# mcu0_primary.net
KiCad netlist of a schematic drawn in Altium Designer
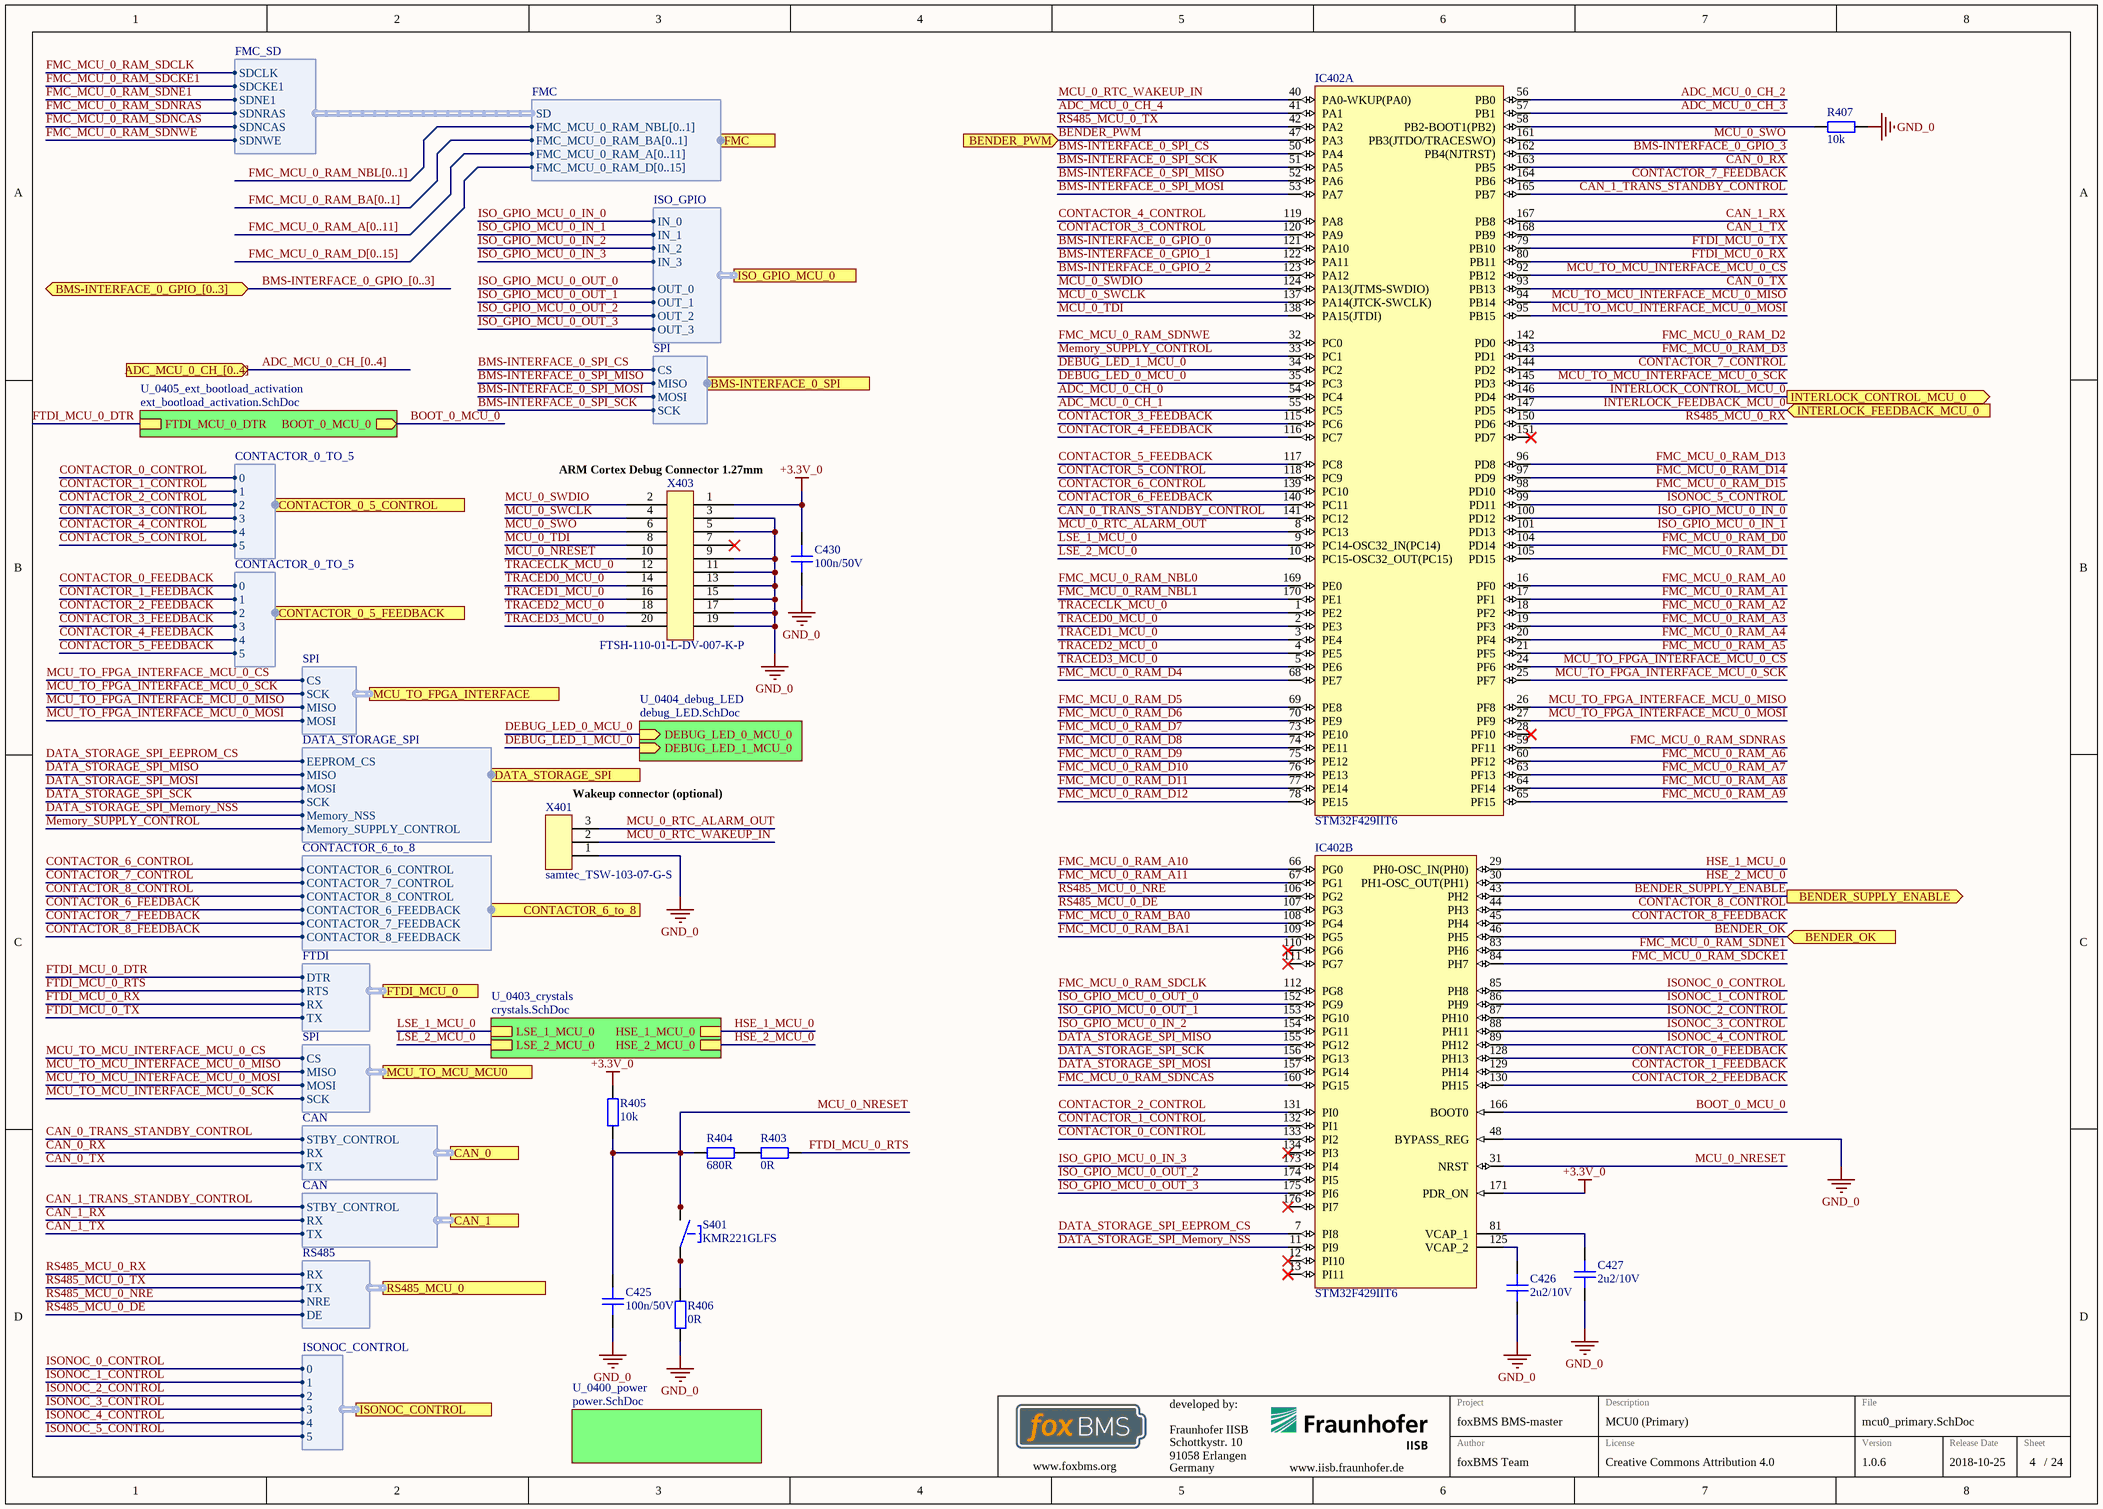
[diagram p0: mcu0_primary.SchDoc]

(export (version "E")
  (design (tool "Eeschema 10.0.6"))
  (components
    (comp (ref "C425")
      (value "100n/50V")
      (footprint "CAPC1608X08N")
      (description "MLCC")
      (fields (field (name "PART NUMBER") "gen_C_ceramic_100n_50V_X7R_0603"))
      (libsource (lib "OE750") (part "C"))
    )
    (comp (ref "C426")
      (value "2u2/10V")
      (footprint "CAPC1608X08N")
      (description "MLCC")
      (fields (field (name "PART NUMBER") "gen_C_ceramic_2u2_10V_X5R_0603"))
      (libsource (lib "OE750") (part "C"))
    )
    (comp (ref "C427")
      (value "2u2/10V")
      (footprint "CAPC1608X08N")
      (description "MLCC")
      (fields (field (name "PART NUMBER") "gen_C_ceramic_2u2_10V_X5R_0603"))
      (libsource (lib "OE750") (part "C"))
    )
    (comp (ref "C430")
      (value "100n/50V")
      (footprint "CAPC1608X08N")
      (description "MLCC")
      (fields (field (name "PART NUMBER") "gen_C_ceramic_100n_50V_X7R_0603"))
      (libsource (lib "OE750") (part "C"))
    )
    (comp (ref "IC402")
      (value "STM32F429IIT6")
      (footprint "STM-LQFP176_N")
      (fields (field (name "MANUFACTURER") "STMicroelectronics"))
      (libsource (lib "Altium Content Vault") (part "MC-ARM-STM32F4X9-SQ176"))
    )
    (comp (ref "R403")
      (value "0R")
      (footprint "RESC1608X05N")
      (description "SMD Resistor 0R 0603")
      (fields (field (name "PART NUMBER") "gen_R_0R_0603") (field (name "POWER") "0.1W"))
      (libsource (lib "OE750") (part "R"))
    )
    (comp (ref "R404")
      (value "680R")
      (footprint "RESC1608X05N")
      (description "SMD Resistor 680R 0603")
      (fields (field (name "PART NUMBER") "gen_R_680R_0603") (field (name "TOLERANCE") "1%"))
      (libsource (lib "OE750") (part "R"))
    )
    (comp (ref "R405")
      (value "10k")
      (footprint "RESC1608X05N")
      (description "SMD Resistor 10k 0603")
      (fields (field (name "PART NUMBER") "gen_R_10k_0603") (field (name "TOLERANCE") "1%"))
      (libsource (lib "OE750") (part "R"))
    )
    (comp (ref "R406")
      (value "0R")
      (footprint "RESC1608X05N")
      (description "SMD Resistor 0R 0603")
      (fields (field (name "PART NUMBER") "gen_R_0R_0603") (field (name "POWER") "0.1W"))
      (libsource (lib "OE750") (part "R"))
    )
    (comp (ref "R407")
      (value "10k")
      (footprint "RESC1608X05N")
      (description "SMD Resistor 10k 0603")
      (fields (field (name "PART NUMBER") "gen_R_10k_0603") (field (name "TOLERANCE") "1%"))
      (libsource (lib "OE750") (part "R"))
    )
    (comp (ref "S401")
      (value "KMR221GLFS")
      (footprint "KMR2_Series")
      (description "Microminiature Tactile Switch")
      (fields (field (name "MANUFACTURER") "CK Components"))
      (libsource (lib "OE750") (part "Switch_4_Pin"))
    )
    (comp (ref "X401")
      (value "samtec_TSW-103-07-G-S")
      (footprint "Pinheader_2.54_3")
      (description "Board-To-Board Connector, Vertical, 2.54 mm, 3 Contacts, Header, TSW Series, Through Hole, 1 Row")
      (fields (field (name "MANUFACTURER") "Samtec"))
      (libsource (lib "OE750") (part "X3"))
    )
    (comp (ref "X403")
      (value "FTSH-110-01-L-DV-007-K-P")
      (footprint "CORTEX_DEBUG_20_PIN")
      (description "Board-To-Board Connector, ARM Cortex Debug Header 20 Pin")
      (fields
        (field (name "PART NUMBER") "samtec_FTSH-110-01-L-DV-007-K-P")
        (field (name "MANUFACTURER") "Samtec")
      )
      (libsource (lib "OE750") (part "CORTEX_DEBUG_20_PIN"))
    )
  )
  (nets
    (net (code "12") (name "+3.3V_0") (class "Default")
      (node (ref "C430") (pin "1") (pinfunction "1_1") (pintype "passive"))
      (node (ref "IC402") (pin "171") (pinfunction "PDR_ON_171") (pintype "input"))
      (node (ref "R405") (pin "2") (pinfunction "2_2") (pintype "passive"))
      (node (ref "X403") (pin "1") (pintype "passive"))
    )
    (net (code "13") (name "/ADC_MCU_0_CH_0") (class "Default")
      (node (ref "IC402") (pin "54") (pinfunction "PC4_54") (pintype "bidirectional"))
    )
    (net (code "14") (name "/ADC_MCU_0_CH_1") (class "Default")
      (node (ref "IC402") (pin "55") (pinfunction "PC5_55") (pintype "bidirectional"))
    )
    (net (code "15") (name "/ADC_MCU_0_CH_2") (class "Default")
      (node (ref "IC402") (pin "56") (pinfunction "PB0_56") (pintype "bidirectional"))
    )
    (net (code "16") (name "/ADC_MCU_0_CH_3") (class "Default")
      (node (ref "IC402") (pin "57") (pinfunction "PB1_57") (pintype "bidirectional"))
    )
    (net (code "17") (name "/ADC_MCU_0_CH_4") (class "Default")
      (node (ref "IC402") (pin "41") (pinfunction "PA1_41") (pintype "bidirectional"))
    )
    (net (code "19") (name "/BENDER_OK") (class "Default")
      (node (ref "IC402") (pin "46") (pinfunction "PH5_46") (pintype "bidirectional"))
    )
    (net (code "20") (name "/BENDER_PWM") (class "Default")
      (node (ref "IC402") (pin "47") (pinfunction "PA3_47") (pintype "bidirectional"))
    )
    (net (code "21") (name "/BENDER_SUPPLY_ENABLE") (class "Default")
      (node (ref "IC402") (pin "43") (pinfunction "PH2_43") (pintype "bidirectional"))
    )
    (net (code "22") (name "/BMS-INTERFACE_0_GPIO_0") (class "Default")
      (node (ref "IC402") (pin "121") (pinfunction "PA10_121") (pintype "bidirectional"))
    )
    (net (code "23") (name "/BMS-INTERFACE_0_GPIO_1") (class "Default")
      (node (ref "IC402") (pin "122") (pinfunction "PA11_122") (pintype "bidirectional"))
    )
    (net (code "24") (name "/BMS-INTERFACE_0_GPIO_2") (class "Default")
      (node (ref "IC402") (pin "123") (pinfunction "PA12_123") (pintype "bidirectional"))
    )
    (net (code "25") (name "/BMS-INTERFACE_0_GPIO_3") (class "Default")
      (node (ref "IC402") (pin "162") (pinfunction "PB4(NJTRST)_162") (pintype "bidirectional"))
    )
    (net (code "27") (name "/BMS-INTERFACE_0_SPI_CS") (class "Default")
      (node (ref "IC402") (pin "50") (pinfunction "PA4_50") (pintype "bidirectional"))
    )
    (net (code "28") (name "/BMS-INTERFACE_0_SPI_MISO") (class "Default")
      (node (ref "IC402") (pin "52") (pinfunction "PA6_52") (pintype "bidirectional"))
    )
    (net (code "29") (name "/BMS-INTERFACE_0_SPI_MOSI") (class "Default")
      (node (ref "IC402") (pin "53") (pinfunction "PA7_53") (pintype "bidirectional"))
    )
    (net (code "30") (name "/BMS-INTERFACE_0_SPI_SCK") (class "Default")
      (node (ref "IC402") (pin "51") (pinfunction "PA5_51") (pintype "bidirectional"))
    )
    (net (code "31") (name "/BOOT_0_MCU_0") (class "Default")
      (node (ref "IC402") (pin "166") (pinfunction "BOOT0_166") (pintype "input"))
    )
    (net (code "32") (name "/CAN_0_RX") (class "Default")
      (node (ref "IC402") (pin "163") (pinfunction "PB5_163") (pintype "bidirectional"))
    )
    (net (code "33") (name "/CAN_0_TRANS_STANDBY_CONTROL") (class "Default")
      (node (ref "IC402") (pin "141") (pinfunction "PC12_141") (pintype "bidirectional"))
    )
    (net (code "34") (name "/CAN_0_TX") (class "Default")
      (node (ref "IC402") (pin "93") (pinfunction "PB13_93") (pintype "bidirectional"))
    )
    (net (code "35") (name "/CAN_1_RX") (class "Default")
      (node (ref "IC402") (pin "167") (pinfunction "PB8_167") (pintype "bidirectional"))
    )
    (net (code "36") (name "/CAN_1_TRANS_STANDBY_CONTROL") (class "Default")
      (node (ref "IC402") (pin "165") (pinfunction "PB7_165") (pintype "bidirectional"))
    )
    (net (code "37") (name "/CAN_1_TX") (class "Default")
      (node (ref "IC402") (pin "168") (pinfunction "PB9_168") (pintype "bidirectional"))
    )
    (net (code "38") (name "/CONTACTOR_0_CONTROL") (class "Default")
      (node (ref "IC402") (pin "133") (pinfunction "PI2_133") (pintype "bidirectional"))
    )
    (net (code "39") (name "/CONTACTOR_0_FEEDBACK") (class "Default")
      (node (ref "IC402") (pin "128") (pinfunction "PH13_128") (pintype "bidirectional"))
    )
    (net (code "40") (name "/CONTACTOR_1_CONTROL") (class "Default")
      (node (ref "IC402") (pin "132") (pinfunction "PI1_132") (pintype "bidirectional"))
    )
    (net (code "41") (name "/CONTACTOR_1_FEEDBACK") (class "Default")
      (node (ref "IC402") (pin "129") (pinfunction "PH14_129") (pintype "bidirectional"))
    )
    (net (code "42") (name "/CONTACTOR_2_CONTROL") (class "Default")
      (node (ref "IC402") (pin "131") (pinfunction "PI0_131") (pintype "bidirectional"))
    )
    (net (code "43") (name "/CONTACTOR_2_FEEDBACK") (class "Default")
      (node (ref "IC402") (pin "130") (pinfunction "PH15_130") (pintype "bidirectional"))
    )
    (net (code "44") (name "/CONTACTOR_3_CONTROL") (class "Default")
      (node (ref "IC402") (pin "120") (pinfunction "PA9_120") (pintype "bidirectional"))
    )
    (net (code "45") (name "/CONTACTOR_3_FEEDBACK") (class "Default")
      (node (ref "IC402") (pin "115") (pinfunction "PC6_115") (pintype "bidirectional"))
    )
    (net (code "46") (name "/CONTACTOR_4_CONTROL") (class "Default")
      (node (ref "IC402") (pin "119") (pinfunction "PA8_119") (pintype "bidirectional"))
    )
    (net (code "47") (name "/CONTACTOR_4_FEEDBACK") (class "Default")
      (node (ref "IC402") (pin "116") (pinfunction "PC7_116") (pintype "bidirectional"))
    )
    (net (code "48") (name "/CONTACTOR_5_CONTROL") (class "Default")
      (node (ref "IC402") (pin "118") (pinfunction "PC9_118") (pintype "bidirectional"))
    )
    (net (code "49") (name "/CONTACTOR_5_FEEDBACK") (class "Default")
      (node (ref "IC402") (pin "117") (pinfunction "PC8_117") (pintype "bidirectional"))
    )
    (net (code "50") (name "/CONTACTOR_6_CONTROL") (class "Default")
      (node (ref "IC402") (pin "139") (pinfunction "PC10_139") (pintype "bidirectional"))
    )
    (net (code "51") (name "/CONTACTOR_6_FEEDBACK") (class "Default")
      (node (ref "IC402") (pin "140") (pinfunction "PC11_140") (pintype "bidirectional"))
    )
    (net (code "52") (name "/CONTACTOR_7_CONTROL") (class "Default")
      (node (ref "IC402") (pin "144") (pinfunction "PD2_144") (pintype "bidirectional"))
    )
    (net (code "53") (name "/CONTACTOR_7_FEEDBACK") (class "Default")
      (node (ref "IC402") (pin "164") (pinfunction "PB6_164") (pintype "bidirectional"))
    )
    (net (code "54") (name "/CONTACTOR_8_CONTROL") (class "Default")
      (node (ref "IC402") (pin "44") (pinfunction "PH3_44") (pintype "bidirectional"))
    )
    (net (code "55") (name "/CONTACTOR_8_FEEDBACK") (class "Default")
      (node (ref "IC402") (pin "45") (pinfunction "PH4_45") (pintype "bidirectional"))
    )
    (net (code "56") (name "/DATA_STORAGE_SPI_EEPROM_CS") (class "Default")
      (node (ref "IC402") (pin "7") (pinfunction "PI8_7") (pintype "bidirectional"))
    )
    (net (code "57") (name "/DATA_STORAGE_SPI_MISO") (class "Default")
      (node (ref "IC402") (pin "155") (pinfunction "PG12_155") (pintype "bidirectional"))
    )
    (net (code "58") (name "/DATA_STORAGE_SPI_MOSI") (class "Default")
      (node (ref "IC402") (pin "157") (pinfunction "PG14_157") (pintype "bidirectional"))
    )
    (net (code "59") (name "/DATA_STORAGE_SPI_Memory_NSS") (class "Default")
      (node (ref "IC402") (pin "11") (pinfunction "PI9_11") (pintype "bidirectional"))
    )
    (net (code "60") (name "/DATA_STORAGE_SPI_SCK") (class "Default")
      (node (ref "IC402") (pin "156") (pinfunction "PG13_156") (pintype "bidirectional"))
    )
    (net (code "61") (name "/DEBUG_LED_0_MCU_0") (class "Default")
      (node (ref "IC402") (pin "35") (pinfunction "PC3_35") (pintype "bidirectional"))
    )
    (net (code "62") (name "/DEBUG_LED_1_MCU_0") (class "Default")
      (node (ref "IC402") (pin "34") (pinfunction "PC2_34") (pintype "bidirectional"))
    )
    (net (code "63") (name "/FMC_MCU_0_RAM_A0") (class "Default")
      (node (ref "IC402") (pin "16") (pinfunction "PF0_16") (pintype "bidirectional"))
    )
    (net (code "64") (name "/FMC_MCU_0_RAM_A1") (class "Default")
      (node (ref "IC402") (pin "17") (pinfunction "PF1_17") (pintype "bidirectional"))
    )
    (net (code "65") (name "/FMC_MCU_0_RAM_A2") (class "Default")
      (node (ref "IC402") (pin "18") (pinfunction "PF2_18") (pintype "bidirectional"))
    )
    (net (code "66") (name "/FMC_MCU_0_RAM_A3") (class "Default")
      (node (ref "IC402") (pin "19") (pinfunction "PF3_19") (pintype "bidirectional"))
    )
    (net (code "67") (name "/FMC_MCU_0_RAM_A4") (class "Default")
      (node (ref "IC402") (pin "20") (pinfunction "PF4_20") (pintype "bidirectional"))
    )
    (net (code "68") (name "/FMC_MCU_0_RAM_A5") (class "Default")
      (node (ref "IC402") (pin "21") (pinfunction "PF5_21") (pintype "bidirectional"))
    )
    (net (code "69") (name "/FMC_MCU_0_RAM_A6") (class "Default")
      (node (ref "IC402") (pin "60") (pinfunction "PF12_60") (pintype "bidirectional"))
    )
    (net (code "70") (name "/FMC_MCU_0_RAM_A7") (class "Default")
      (node (ref "IC402") (pin "63") (pinfunction "PF13_63") (pintype "bidirectional"))
    )
    (net (code "71") (name "/FMC_MCU_0_RAM_A8") (class "Default")
      (node (ref "IC402") (pin "64") (pinfunction "PF14_64") (pintype "bidirectional"))
    )
    (net (code "72") (name "/FMC_MCU_0_RAM_A9") (class "Default")
      (node (ref "IC402") (pin "65") (pinfunction "PF15_65") (pintype "bidirectional"))
    )
    (net (code "73") (name "/FMC_MCU_0_RAM_A10") (class "Default")
      (node (ref "IC402") (pin "66") (pinfunction "PG0_66") (pintype "bidirectional"))
    )
    (net (code "74") (name "/FMC_MCU_0_RAM_A11") (class "Default")
      (node (ref "IC402") (pin "67") (pinfunction "PG1_67") (pintype "bidirectional"))
    )
    (net (code "76") (name "/FMC_MCU_0_RAM_BA0") (class "Default")
      (node (ref "IC402") (pin "108") (pinfunction "PG4_108") (pintype "bidirectional"))
    )
    (net (code "77") (name "/FMC_MCU_0_RAM_BA1") (class "Default")
      (node (ref "IC402") (pin "109") (pinfunction "PG5_109") (pintype "bidirectional"))
    )
    (net (code "79") (name "/FMC_MCU_0_RAM_D0") (class "Default")
      (node (ref "IC402") (pin "104") (pinfunction "PD14_104") (pintype "bidirectional"))
    )
    (net (code "80") (name "/FMC_MCU_0_RAM_D1") (class "Default")
      (node (ref "IC402") (pin "105") (pinfunction "PD15_105") (pintype "bidirectional"))
    )
    (net (code "81") (name "/FMC_MCU_0_RAM_D2") (class "Default")
      (node (ref "IC402") (pin "142") (pinfunction "PD0_142") (pintype "bidirectional"))
    )
    (net (code "82") (name "/FMC_MCU_0_RAM_D3") (class "Default")
      (node (ref "IC402") (pin "143") (pinfunction "PD1_143") (pintype "bidirectional"))
    )
    (net (code "83") (name "/FMC_MCU_0_RAM_D4") (class "Default")
      (node (ref "IC402") (pin "68") (pinfunction "PE7_68") (pintype "bidirectional"))
    )
    (net (code "84") (name "/FMC_MCU_0_RAM_D5") (class "Default")
      (node (ref "IC402") (pin "69") (pinfunction "PE8_69") (pintype "bidirectional"))
    )
    (net (code "85") (name "/FMC_MCU_0_RAM_D6") (class "Default")
      (node (ref "IC402") (pin "70") (pinfunction "PE9_70") (pintype "bidirectional"))
    )
    (net (code "86") (name "/FMC_MCU_0_RAM_D7") (class "Default")
      (node (ref "IC402") (pin "73") (pinfunction "PE10_73") (pintype "bidirectional"))
    )
    (net (code "87") (name "/FMC_MCU_0_RAM_D8") (class "Default")
      (node (ref "IC402") (pin "74") (pinfunction "PE11_74") (pintype "bidirectional"))
    )
    (net (code "88") (name "/FMC_MCU_0_RAM_D9") (class "Default")
      (node (ref "IC402") (pin "75") (pinfunction "PE12_75") (pintype "bidirectional"))
    )
    (net (code "89") (name "/FMC_MCU_0_RAM_D10") (class "Default")
      (node (ref "IC402") (pin "76") (pinfunction "PE13_76") (pintype "bidirectional"))
    )
    (net (code "90") (name "/FMC_MCU_0_RAM_D11") (class "Default")
      (node (ref "IC402") (pin "77") (pinfunction "PE14_77") (pintype "bidirectional"))
    )
    (net (code "91") (name "/FMC_MCU_0_RAM_D12") (class "Default")
      (node (ref "IC402") (pin "78") (pinfunction "PE15_78") (pintype "bidirectional"))
    )
    (net (code "92") (name "/FMC_MCU_0_RAM_D13") (class "Default")
      (node (ref "IC402") (pin "96") (pinfunction "PD8_96") (pintype "bidirectional"))
    )
    (net (code "93") (name "/FMC_MCU_0_RAM_D14") (class "Default")
      (node (ref "IC402") (pin "97") (pinfunction "PD9_97") (pintype "bidirectional"))
    )
    (net (code "94") (name "/FMC_MCU_0_RAM_D15") (class "Default")
      (node (ref "IC402") (pin "98") (pinfunction "PD10_98") (pintype "bidirectional"))
    )
    (net (code "95") (name "/FMC_MCU_0_RAM_NBL0") (class "Default")
      (node (ref "IC402") (pin "169") (pinfunction "PE0_169") (pintype "bidirectional"))
    )
    (net (code "96") (name "/FMC_MCU_0_RAM_NBL1") (class "Default")
      (node (ref "IC402") (pin "170") (pinfunction "PE1_170") (pintype "bidirectional"))
    )
    (net (code "98") (name "/FMC_MCU_0_RAM_SDCKE1") (class "Default")
      (node (ref "IC402") (pin "84") (pinfunction "PH7_84") (pintype "bidirectional"))
    )
    (net (code "99") (name "/FMC_MCU_0_RAM_SDCLK") (class "Default")
      (node (ref "IC402") (pin "112") (pinfunction "PG8_112") (pintype "bidirectional"))
    )
    (net (code "100") (name "/FMC_MCU_0_RAM_SDNCAS") (class "Default")
      (node (ref "IC402") (pin "160") (pinfunction "PG15_160") (pintype "bidirectional"))
    )
    (net (code "101") (name "/FMC_MCU_0_RAM_SDNE1") (class "Default")
      (node (ref "IC402") (pin "83") (pinfunction "PH6_83") (pintype "bidirectional"))
    )
    (net (code "102") (name "/FMC_MCU_0_RAM_SDNRAS") (class "Default")
      (node (ref "IC402") (pin "59") (pinfunction "PF11_59") (pintype "bidirectional"))
    )
    (net (code "103") (name "/FMC_MCU_0_RAM_SDNWE") (class "Default")
      (node (ref "IC402") (pin "32") (pinfunction "PC0_32") (pintype "bidirectional"))
    )
    (net (code "106") (name "/FTDI_MCU_0_RTS") (class "Default")
      (node (ref "R403") (pin "2") (pinfunction "2_2") (pintype "passive"))
    )
    (net (code "107") (name "/FTDI_MCU_0_RX") (class "Default")
      (node (ref "IC402") (pin "80") (pinfunction "PB11_80") (pintype "bidirectional"))
    )
    (net (code "108") (name "/FTDI_MCU_0_TX") (class "Default")
      (node (ref "IC402") (pin "79") (pinfunction "PB10_79") (pintype "bidirectional"))
    )
    (net (code "109") (name "/HSE_1_MCU_0") (class "Default")
      (node (ref "IC402") (pin "29") (pinfunction "PH0-OSC_IN(PH0)_29") (pintype "bidirectional"))
    )
    (net (code "110") (name "/HSE_2_MCU_0") (class "Default")
      (node (ref "IC402") (pin "30") (pinfunction "PH1-OSC_OUT(PH1)_30") (pintype "bidirectional"))
    )
    (net (code "111") (name "/INTERLOCK_CONTROL_MCU_0") (class "Default")
      (node (ref "IC402") (pin "146") (pinfunction "PD4_146") (pintype "bidirectional"))
    )
    (net (code "112") (name "/INTERLOCK_FEEDBACK_MCU_0") (class "Default")
      (node (ref "IC402") (pin "147") (pinfunction "PD5_147") (pintype "bidirectional"))
    )
    (net (code "113") (name "/ISONOC_0_CONTROL") (class "Default")
      (node (ref "IC402") (pin "85") (pinfunction "PH8_85") (pintype "bidirectional"))
    )
    (net (code "114") (name "/ISONOC_1_CONTROL") (class "Default")
      (node (ref "IC402") (pin "86") (pinfunction "PH9_86") (pintype "bidirectional"))
    )
    (net (code "115") (name "/ISONOC_2_CONTROL") (class "Default")
      (node (ref "IC402") (pin "87") (pinfunction "PH10_87") (pintype "bidirectional"))
    )
    (net (code "116") (name "/ISONOC_3_CONTROL") (class "Default")
      (node (ref "IC402") (pin "88") (pinfunction "PH11_88") (pintype "bidirectional"))
    )
    (net (code "117") (name "/ISONOC_4_CONTROL") (class "Default")
      (node (ref "IC402") (pin "89") (pinfunction "PH12_89") (pintype "bidirectional"))
    )
    (net (code "118") (name "/ISONOC_5_CONTROL") (class "Default")
      (node (ref "IC402") (pin "99") (pinfunction "PD11_99") (pintype "bidirectional"))
    )
    (net (code "119") (name "/ISO_GPIO_MCU_0_IN_0") (class "Default")
      (node (ref "IC402") (pin "100") (pinfunction "PD12_100") (pintype "bidirectional"))
    )
    (net (code "120") (name "/ISO_GPIO_MCU_0_IN_1") (class "Default")
      (node (ref "IC402") (pin "101") (pinfunction "PD13_101") (pintype "bidirectional"))
    )
    (net (code "121") (name "/ISO_GPIO_MCU_0_IN_2") (class "Default")
      (node (ref "IC402") (pin "154") (pinfunction "PG11_154") (pintype "bidirectional"))
    )
    (net (code "122") (name "/ISO_GPIO_MCU_0_IN_3") (class "Default")
      (node (ref "IC402") (pin "173") (pinfunction "PI4_173") (pintype "bidirectional"))
    )
    (net (code "123") (name "/ISO_GPIO_MCU_0_OUT_0") (class "Default")
      (node (ref "IC402") (pin "152") (pinfunction "PG9_152") (pintype "bidirectional"))
    )
    (net (code "124") (name "/ISO_GPIO_MCU_0_OUT_1") (class "Default")
      (node (ref "IC402") (pin "153") (pinfunction "PG10_153") (pintype "bidirectional"))
    )
    (net (code "125") (name "/ISO_GPIO_MCU_0_OUT_2") (class "Default")
      (node (ref "IC402") (pin "174") (pinfunction "PI5_174") (pintype "bidirectional"))
    )
    (net (code "126") (name "/ISO_GPIO_MCU_0_OUT_3") (class "Default")
      (node (ref "IC402") (pin "175") (pinfunction "PI6_175") (pintype "bidirectional"))
    )
    (net (code "127") (name "/LSE_1_MCU_0") (class "Default")
      (node (ref "IC402") (pin "9") (pinfunction "PC14-OSC32_IN(PC14)_9") (pintype "bidirectional"))
    )
    (net (code "128") (name "/LSE_2_MCU_0") (class "Default")
      (node (ref "IC402") (pin "10") (pinfunction "PC15-OSC32_OUT(PC15)_10") (pintype "bidirectional"))
    )
    (net (code "129") (name "/MCU_0_NRESET") (class "Default")
      (node (ref "C425") (pin "1") (pinfunction "1_1") (pintype "passive"))
      (node (ref "IC402") (pin "31") (pinfunction "NRST_31") (pintype "bidirectional"))
      (node (ref "R404") (pin "1") (pinfunction "1_1") (pintype "passive"))
      (node (ref "R405") (pin "1") (pinfunction "1_1") (pintype "passive"))
      (node (ref "S401") (pin "3") (pintype "passive"))
      (node (ref "S401") (pin "4") (pintype "passive"))
      (node (ref "X403") (pin "10") (pintype "passive"))
    )
    (net (code "130") (name "/MCU_0_RTC_ALARM_OUT") (class "Default")
      (node (ref "IC402") (pin "8") (pinfunction "PC13_8") (pintype "bidirectional"))
      (node (ref "X401") (pin "3") (pintype "passive"))
    )
    (net (code "131") (name "/MCU_0_RTC_WAKEUP_IN") (class "Default")
      (node (ref "IC402") (pin "40") (pinfunction "PA0-WKUP(PA0)_40") (pintype "bidirectional"))
      (node (ref "X401") (pin "2") (pintype "passive"))
    )
    (net (code "132") (name "/MCU_0_SWCLK") (class "Default")
      (node (ref "IC402") (pin "137") (pinfunction "PA14(JTCK-SWCLK)_137") (pintype "bidirectional"))
      (node (ref "X403") (pin "4") (pintype "passive"))
    )
    (net (code "133") (name "/MCU_0_SWDIO") (class "Default")
      (node (ref "IC402") (pin "124") (pinfunction "PA13(JTMS-SWDIO)_124") (pintype "bidirectional"))
      (node (ref "X403") (pin "2") (pintype "passive"))
    )
    (net (code "134") (name "/MCU_0_SWO") (class "Default")
      (node (ref "IC402") (pin "161") (pinfunction "PB3(JTDO/TRACESWO)_161") (pintype "bidirectional"))
      (node (ref "X403") (pin "6") (pintype "passive"))
    )
    (net (code "135") (name "/MCU_0_TDI") (class "Default")
      (node (ref "IC402") (pin "138") (pinfunction "PA15(JTDI)_138") (pintype "bidirectional"))
      (node (ref "X403") (pin "8") (pintype "passive"))
    )
    (net (code "136") (name "/MCU_TO_FPGA_INTERFACE_MCU_0_CS") (class "Default")
      (node (ref "IC402") (pin "24") (pinfunction "PF6_24") (pintype "bidirectional"))
    )
    (net (code "137") (name "/MCU_TO_FPGA_INTERFACE_MCU_0_MISO") (class "Default")
      (node (ref "IC402") (pin "26") (pinfunction "PF8_26") (pintype "bidirectional"))
    )
    (net (code "138") (name "/MCU_TO_FPGA_INTERFACE_MCU_0_MOSI") (class "Default")
      (node (ref "IC402") (pin "27") (pinfunction "PF9_27") (pintype "bidirectional"))
    )
    (net (code "139") (name "/MCU_TO_FPGA_INTERFACE_MCU_0_SCK") (class "Default")
      (node (ref "IC402") (pin "25") (pinfunction "PF7_25") (pintype "bidirectional"))
    )
    (net (code "140") (name "/MCU_TO_MCU_INTERFACE_MCU_0_CS") (class "Default")
      (node (ref "IC402") (pin "92") (pinfunction "PB12_92") (pintype "bidirectional"))
    )
    (net (code "141") (name "/MCU_TO_MCU_INTERFACE_MCU_0_MISO") (class "Default")
      (node (ref "IC402") (pin "94") (pinfunction "PB14_94") (pintype "bidirectional"))
    )
    (net (code "142") (name "/MCU_TO_MCU_INTERFACE_MCU_0_MOSI") (class "Default")
      (node (ref "IC402") (pin "95") (pinfunction "PB15_95") (pintype "bidirectional"))
    )
    (net (code "143") (name "/MCU_TO_MCU_INTERFACE_MCU_0_SCK") (class "Default")
      (node (ref "IC402") (pin "145") (pinfunction "PD3_145") (pintype "bidirectional"))
    )
    (net (code "144") (name "/Memory_SUPPLY_CONTROL") (class "Default")
      (node (ref "IC402") (pin "33") (pinfunction "PC1_33") (pintype "bidirectional"))
    )
    (net (code "145") (name "/RS485_MCU_0_DE") (class "Default")
      (node (ref "IC402") (pin "107") (pinfunction "PG3_107") (pintype "bidirectional"))
    )
    (net (code "146") (name "/RS485_MCU_0_NRE") (class "Default")
      (node (ref "IC402") (pin "106") (pinfunction "PG2_106") (pintype "bidirectional"))
    )
    (net (code "147") (name "/RS485_MCU_0_RX") (class "Default")
      (node (ref "IC402") (pin "150") (pinfunction "PD6_150") (pintype "bidirectional"))
    )
    (net (code "148") (name "/RS485_MCU_0_TX") (class "Default")
      (node (ref "IC402") (pin "42") (pinfunction "PA2_42") (pintype "bidirectional"))
    )
    (net (code "149") (name "/TRACECLK_MCU_0") (class "Default")
      (node (ref "IC402") (pin "1") (pinfunction "PE2_1") (pintype "bidirectional"))
      (node (ref "X403") (pin "12") (pintype "passive"))
    )
    (net (code "150") (name "/TRACED0_MCU_0") (class "Default")
      (node (ref "IC402") (pin "2") (pinfunction "PE3_2") (pintype "bidirectional"))
      (node (ref "X403") (pin "14") (pintype "passive"))
    )
    (net (code "151") (name "/TRACED1_MCU_0") (class "Default")
      (node (ref "IC402") (pin "3") (pinfunction "PE4_3") (pintype "bidirectional"))
      (node (ref "X403") (pin "16") (pintype "passive"))
    )
    (net (code "152") (name "/TRACED2_MCU_0") (class "Default")
      (node (ref "IC402") (pin "4") (pinfunction "PE5_4") (pintype "bidirectional"))
      (node (ref "X403") (pin "18") (pintype "passive"))
    )
    (net (code "153") (name "/TRACED3_MCU_0") (class "Default")
      (node (ref "IC402") (pin "5") (pinfunction "PE6_5") (pintype "bidirectional"))
      (node (ref "X403") (pin "20") (pintype "passive"))
    )
    (net (code "164") (name "GND_0") (class "Default")
      (node (ref "C425") (pin "2") (pinfunction "2_2") (pintype "passive"))
      (node (ref "C426") (pin "2") (pinfunction "2_2") (pintype "passive"))
      (node (ref "C427") (pin "2") (pinfunction "2_2") (pintype "passive"))
      (node (ref "C430") (pin "2") (pinfunction "2_2") (pintype "passive"))
      (node (ref "IC402") (pin "48") (pinfunction "BYPASS_REG_48") (pintype "input"))
      (node (ref "R406") (pin "1") (pinfunction "1_1") (pintype "passive"))
      (node (ref "R407") (pin "1") (pinfunction "1_1") (pintype "passive"))
      (node (ref "X401") (pin "1") (pintype "passive"))
      (node (ref "X403") (pin "11") (pintype "passive"))
      (node (ref "X403") (pin "13") (pintype "passive"))
      (node (ref "X403") (pin "15") (pintype "passive"))
      (node (ref "X403") (pin "17") (pintype "passive"))
      (node (ref "X403") (pin "19") (pintype "passive"))
      (node (ref "X403") (pin "3") (pintype "passive"))
      (node (ref "X403") (pin "5") (pintype "passive"))
      (node (ref "X403") (pin "9") (pintype "passive"))
    )
    (net (code "165") (name "Net-(IC402A-PB2-BOOT1(PB2))") (class "Default")
      (node (ref "IC402") (pin "58") (pinfunction "PB2-BOOT1(PB2)_58") (pintype "bidirectional"))
      (node (ref "R407") (pin "2") (pinfunction "2_2") (pintype "passive"))
    )
    (net (code "166") (name "Net-(IC402B-VCAP_1)") (class "Default")
      (node (ref "C427") (pin "1") (pinfunction "1_1") (pintype "passive"))
      (node (ref "IC402") (pin "81") (pinfunction "VCAP_1_81") (pintype "power_in"))
    )
    (net (code "167") (name "Net-(IC402B-VCAP_2)") (class "Default")
      (node (ref "C426") (pin "1") (pinfunction "1_1") (pintype "passive"))
      (node (ref "IC402") (pin "125") (pinfunction "VCAP_2_125") (pintype "power_in"))
    )
    (net (code "168") (name "Net-(R403-Pad1)") (class "Default")
      (node (ref "R403") (pin "1") (pinfunction "1_1") (pintype "passive"))
      (node (ref "R404") (pin "2") (pinfunction "2_2") (pintype "passive"))
    )
    (net (code "169") (name "Net-(R406-Pad2)") (class "Default")
      (node (ref "R406") (pin "2") (pinfunction "2_2") (pintype "passive"))
      (node (ref "S401") (pin "1") (pintype "passive"))
      (node (ref "S401") (pin "2") (pintype "passive"))
    )
    (net (code "170") (name "unconnected-(IC402A-PD7-Pad151)") (class "Default")
      (node (ref "IC402") (pin "151") (pinfunction "PD7_151") (pintype "bidirectional+no_connect"))
    )
    (net (code "171") (name "unconnected-(IC402A-PF10-Pad28)") (class "Default")
      (node (ref "IC402") (pin "28") (pinfunction "PF10_28") (pintype "bidirectional+no_connect"))
    )
    (net (code "172") (name "unconnected-(IC402B-PG6-Pad110)") (class "Default")
      (node (ref "IC402") (pin "110") (pinfunction "PG6_110") (pintype "bidirectional+no_connect"))
    )
    (net (code "173") (name "unconnected-(IC402B-PG7-Pad111)") (class "Default")
      (node (ref "IC402") (pin "111") (pinfunction "PG7_111") (pintype "bidirectional+no_connect"))
    )
    (net (code "174") (name "unconnected-(IC402B-PI3-Pad134)") (class "Default")
      (node (ref "IC402") (pin "134") (pinfunction "PI3_134") (pintype "bidirectional+no_connect"))
    )
    (net (code "175") (name "unconnected-(IC402B-PI7-Pad176)") (class "Default")
      (node (ref "IC402") (pin "176") (pinfunction "PI7_176") (pintype "bidirectional+no_connect"))
    )
    (net (code "176") (name "unconnected-(IC402B-PI10-Pad12)") (class "Default")
      (node (ref "IC402") (pin "12") (pinfunction "PI10_12") (pintype "bidirectional+no_connect"))
    )
    (net (code "177") (name "unconnected-(IC402B-PI11-Pad13)") (class "Default")
      (node (ref "IC402") (pin "13") (pinfunction "PI11_13") (pintype "bidirectional+no_connect"))
    )
    (net (code "178") (name "unconnected-(X403-Pad7)") (class "Default")
      (node (ref "X403") (pin "7") (pintype "passive+no_connect"))
    )
  )
)
